# 629-test_v1_0.net
KiCad netlist of a schematic drawn in EAGLE
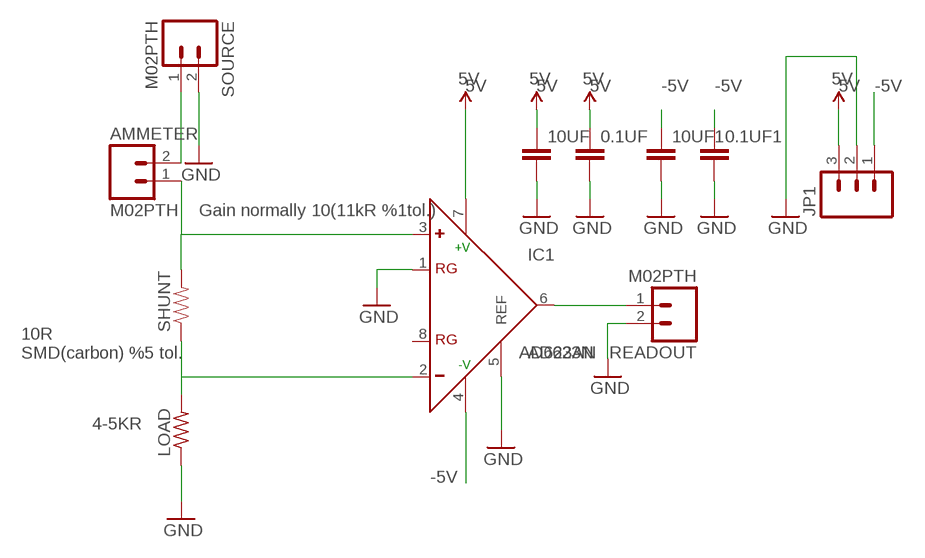
[diagram p0: schematic, sheet 1]

(export (version "E")
  (design (tool "Eeschema 10.0.6"))
  (components
    (comp (ref "0.1UF")
      (value "CAPPTH1")
      (footprint "eagle-import:CAP-PTH-5MM")
      (libsource (lib "eagle-import") (part "CAPPTH1"))
    )
    (comp (ref "0.1UF1")
      (value "CAPPTH1")
      (footprint "eagle-import:CAP-PTH-5MM")
      (libsource (lib "eagle-import") (part "CAPPTH1"))
    )
    (comp (ref "10UF")
      (value "CAPPTH1")
      (footprint "eagle-import:CAP-PTH-5MM")
      (libsource (lib "eagle-import") (part "CAPPTH1"))
    )
    (comp (ref "10UF1")
      (value "CAPPTH1")
      (footprint "eagle-import:CAP-PTH-5MM")
      (libsource (lib "eagle-import") (part "CAPPTH1"))
    )
    (comp (ref "AMMETER")
      (value "M02PTH")
      (footprint "eagle-import:1X02")
      (libsource (lib "eagle-import") (part "M02PTH"))
    )
    (comp (ref "IC1")
      (value "AD623N")
      (footprint "eagle-import:DIL08")
      (fields (field (name "MF") "ALTERA CORPORATION") (field (name "MPN") "AD623ANZ"))
      (libsource (lib "eagle-import") (part "AD623N"))
    )
    (comp (ref "JP1")
      (value "M03LOCK")
      (footprint "eagle-import:1X03_LOCK")
      (libsource (lib "eagle-import") (part "M03LOCK"))
    )
    (comp (ref "LOAD")
      (value "R-US_0207/10")
      (footprint "eagle-import:0207_10")
      (libsource (lib "eagle-import") (part "R-US_0207/10"))
    )
    (comp (ref "READOUT")
      (value "M02PTH")
      (footprint "eagle-import:1X02")
      (libsource (lib "eagle-import") (part "M02PTH"))
    )
    (comp (ref "SHUNT")
      (value "RESISTOR1206")
      (footprint "eagle-import:1206")
      (libsource (lib "eagle-import") (part "RESISTOR1206"))
    )
    (comp (ref "SOURCE")
      (value "M02PTH")
      (footprint "eagle-import:1X02")
      (libsource (lib "eagle-import") (part "M02PTH"))
    )
  )
  (nets
    (net (code "1") (name "/-5V") (class "Default")
      (node (ref "0.1UF1") (pin "1") (pinfunction "1_1") (pintype "passive"))
      (node (ref "10UF1") (pin "1") (pinfunction "1_1") (pintype "passive"))
      (node (ref "IC1") (pin "4") (pinfunction "-V_4") (pintype "power_in"))
      (node (ref "JP1") (pin "1") (pinfunction "1_1") (pintype "passive"))
    )
    (net (code "2") (name "5V") (class "Default")
      (node (ref "0.1UF") (pin "1") (pinfunction "1_1") (pintype "passive"))
      (node (ref "10UF") (pin "1") (pinfunction "1_1") (pintype "passive"))
      (node (ref "IC1") (pin "7") (pinfunction "+V_7") (pintype "power_in"))
      (node (ref "JP1") (pin "3") (pinfunction "3_3") (pintype "passive"))
    )
    (net (code "3") (name "GND") (class "Default")
      (node (ref "0.1UF") (pin "2") (pinfunction "2_2") (pintype "passive"))
      (node (ref "0.1UF1") (pin "2") (pinfunction "2_2") (pintype "passive"))
      (node (ref "10UF") (pin "2") (pinfunction "2_2") (pintype "passive"))
      (node (ref "10UF1") (pin "2") (pinfunction "2_2") (pintype "passive"))
      (node (ref "IC1") (pin "1") (pinfunction "RG_1") (pintype "passive"))
      (node (ref "IC1") (pin "5") (pinfunction "REF_5") (pintype "passive"))
      (node (ref "JP1") (pin "2") (pinfunction "2_2") (pintype "passive"))
      (node (ref "LOAD") (pin "1") (pinfunction "1_1") (pintype "passive"))
      (node (ref "READOUT") (pin "2") (pinfunction "2_2") (pintype "passive"))
      (node (ref "SOURCE") (pin "2") (pinfunction "2_2") (pintype "passive"))
    )
    (net (code "4") (name "Net-(AMMETER-Pad2)") (class "Default")
      (node (ref "AMMETER") (pin "2") (pinfunction "2_2") (pintype "passive"))
      (node (ref "SOURCE") (pin "1") (pinfunction "1_1") (pintype "passive"))
    )
    (net (code "5") (name "Net-(IC1-+)") (class "Default")
      (node (ref "AMMETER") (pin "1") (pinfunction "1_1") (pintype "passive"))
      (node (ref "IC1") (pin "3") (pinfunction "+_3") (pintype "input"))
      (node (ref "SHUNT") (pin "2") (pinfunction "2_2") (pintype "passive"))
    )
    (net (code "6") (name "Net-(IC1--)") (class "Default")
      (node (ref "IC1") (pin "2") (pinfunction "-_2") (pintype "input"))
      (node (ref "LOAD") (pin "2") (pinfunction "2_2") (pintype "passive"))
      (node (ref "SHUNT") (pin "1") (pinfunction "1_1") (pintype "passive"))
    )
    (net (code "7") (name "Net-(IC1-OUT)") (class "Default")
      (node (ref "IC1") (pin "6") (pinfunction "OUT_6") (pintype "output"))
      (node (ref "READOUT") (pin "1") (pinfunction "1_1") (pintype "passive"))
    )
    (net (code "8") (name "unconnected-(IC1-RG-Pad8)") (class "Default")
      (node (ref "IC1") (pin "8") (pinfunction "RG_8") (pintype "passive"))
    )
  )
)
